# Storage.net
KiCad netlist of a schematic drawn in Altium Designer
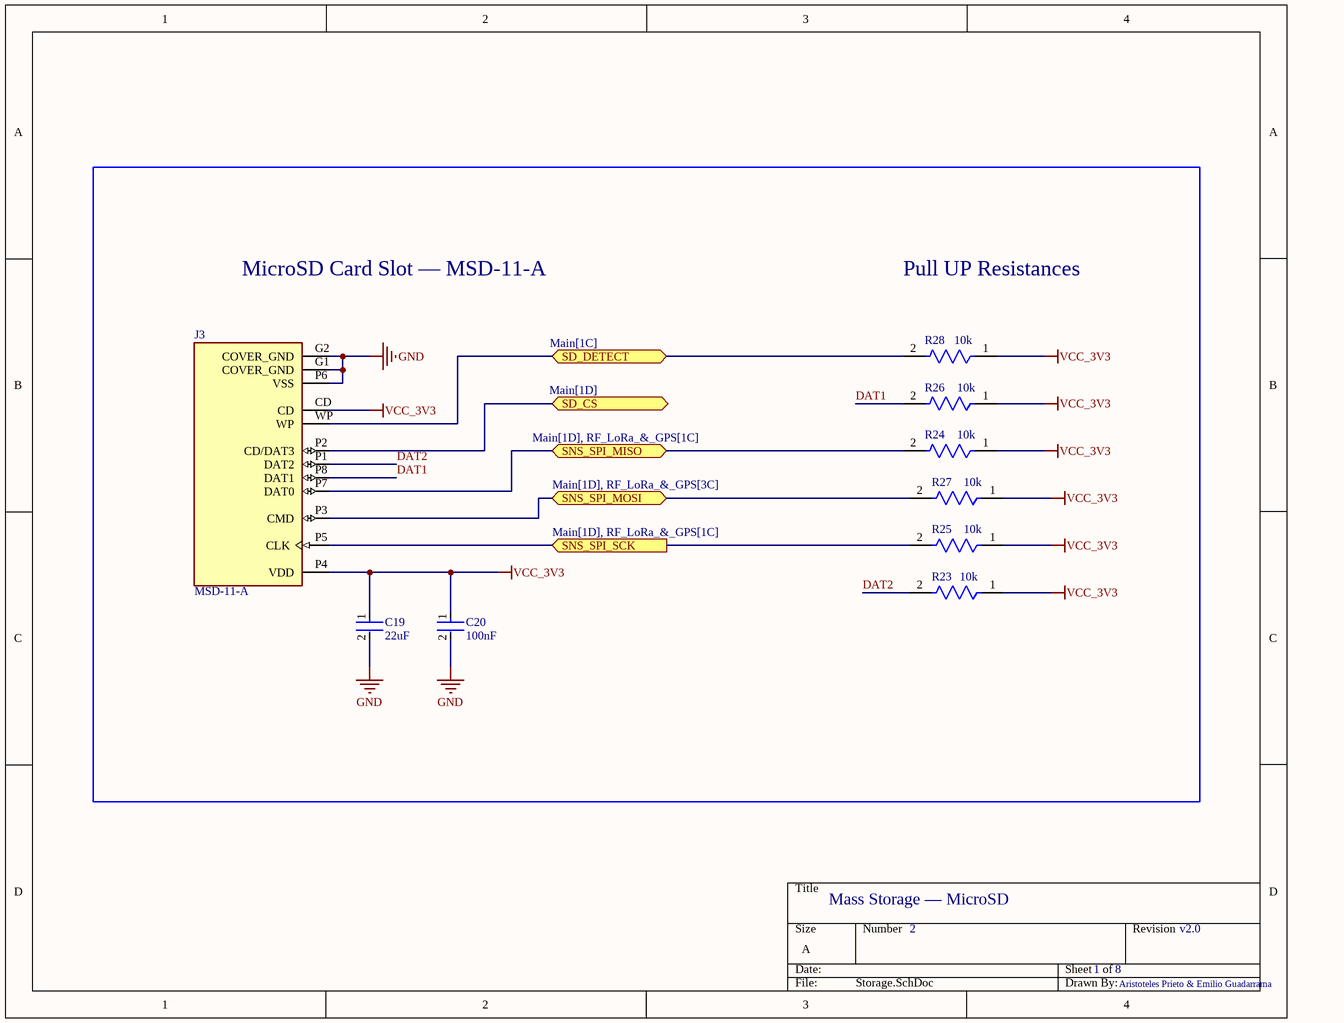
[diagram p0: Storage.SchDoc]

(export (version "E")
  (design (tool "Eeschema 10.0.6"))
  (components
    (comp (ref "C19")
      (value "22uF")
      (footprint "FP-C0805C-DN-MFG")
      (description "CAP CER 0.1UF 50V X7R 0805")
      (fields
        (field (name "MANUFACTURER PART NUMBER") "C0805C104K5RACTU")
        (field (name "MANUFACTURER") "KEMET")
      )
      (libsource (lib "Altium Content Vault") (part "b4654b650e69147ec39a6b967a45e02"))
    )
    (comp (ref "C20")
      (value "100nF")
      (footprint "FP-C0805C-DN-MFG")
      (description "CAP CER 0.1UF 50V X7R 0805")
      (fields
        (field (name "MANUFACTURER PART NUMBER") "C0805C104K5RACTU")
        (field (name "MANUFACTURER") "KEMET")
      )
      (libsource (lib "Altium Content Vault") (part "b4654b650e69147ec39a6b967a45e02"))
    )
    (comp (ref "J3")
      (value "MSD-11-A")
      (footprint "CUI_MSD-11-A")
      (fields (field (name "MF") "Same Sky"))
      (libsource (lib "SD_Holder-MSD-11-A") (part "MSD-11-A"))
    )
    (comp (ref "R23")
      (value "10k")
      (footprint "FP-MCT0603-IPC_A")
      (description "RES SMD 100 OHM 1% 1/8W 0603")
      (fields (field (name "TOLERANCE") "0.1%"))
      (libsource (lib "Altium Content Vault") (part "1029c3af85768c4190bb7ad29bc67b5"))
    )
    (comp (ref "R24")
      (value "10k")
      (footprint "FP-MCT0603-IPC_A")
      (description "RES SMD 100 OHM 1% 1/8W 0603")
      (fields (field (name "TOLERANCE") "0.1%"))
      (libsource (lib "Altium Content Vault") (part "1029c3af85768c4190bb7ad29bc67b5"))
    )
    (comp (ref "R25")
      (value "10k")
      (footprint "FP-MCT0603-IPC_A")
      (description "RES SMD 100 OHM 1% 1/8W 0603")
      (fields (field (name "TOLERANCE") "0.1%"))
      (libsource (lib "Altium Content Vault") (part "1029c3af85768c4190bb7ad29bc67b5"))
    )
    (comp (ref "R26")
      (value "10k")
      (footprint "FP-MCT0603-IPC_A")
      (description "RES SMD 100 OHM 1% 1/8W 0603")
      (fields (field (name "TOLERANCE") "0.1%"))
      (libsource (lib "Altium Content Vault") (part "1029c3af85768c4190bb7ad29bc67b5"))
    )
    (comp (ref "R27")
      (value "10k")
      (footprint "FP-MCT0603-IPC_A")
      (description "RES SMD 100 OHM 1% 1/8W 0603")
      (fields (field (name "TOLERANCE") "0.1%"))
      (libsource (lib "Altium Content Vault") (part "1029c3af85768c4190bb7ad29bc67b5"))
    )
    (comp (ref "R28")
      (value "10k")
      (footprint "FP-MCT0603-IPC_A")
      (description "RES SMD 100 OHM 1% 1/8W 0603")
      (fields (field (name "TOLERANCE") "0.1%"))
      (libsource (lib "Altium Content Vault") (part "1029c3af85768c4190bb7ad29bc67b5"))
    )
  )
  (nets
    (net (code "1") (name "/DAT1") (class "Default")
      (node (ref "J3") (pin "P8") (pinfunction "DAT1_P8") (pintype "bidirectional"))
      (node (ref "R26") (pin "2") (pinfunction "2_2") (pintype "passive"))
    )
    (net (code "2") (name "/DAT2") (class "Default")
      (node (ref "J3") (pin "P1") (pinfunction "DAT2_P1") (pintype "bidirectional"))
      (node (ref "R23") (pin "2") (pinfunction "2_2") (pintype "passive"))
    )
    (net (code "3") (name "/SD_CS") (class "Default")
      (node (ref "J3") (pin "P2") (pinfunction "CD/DAT3_P2") (pintype "bidirectional"))
    )
    (net (code "4") (name "/SD_DETECT") (class "Default")
      (node (ref "J3") (pin "WP") (pinfunction "WP_WP") (pintype "passive"))
      (node (ref "R28") (pin "2") (pinfunction "2_2") (pintype "passive"))
    )
    (net (code "5") (name "/SNS_SPI_MISO") (class "Default")
      (node (ref "J3") (pin "P7") (pinfunction "DAT0_P7") (pintype "bidirectional"))
      (node (ref "R24") (pin "2") (pinfunction "2_2") (pintype "passive"))
    )
    (net (code "6") (name "/SNS_SPI_MOSI") (class "Default")
      (node (ref "J3") (pin "P3") (pinfunction "CMD_P3") (pintype "bidirectional"))
      (node (ref "R27") (pin "2") (pinfunction "2_2") (pintype "passive"))
    )
    (net (code "7") (name "/SNS_SPI_SCK") (class "Default")
      (node (ref "J3") (pin "P5") (pinfunction "CLK_P5") (pintype "input"))
      (node (ref "R25") (pin "2") (pinfunction "2_2") (pintype "passive"))
    )
    (net (code "8") (name "GND") (class "Default")
      (node (ref "C19") (pin "2") (pinfunction "2_2") (pintype "passive"))
      (node (ref "C20") (pin "2") (pinfunction "2_2") (pintype "passive"))
      (node (ref "J3") (pin "G1") (pinfunction "COVER_GND_G1") (pintype "power_in"))
      (node (ref "J3") (pin "G2") (pinfunction "COVER_GND_G2") (pintype "power_in"))
      (node (ref "J3") (pin "P6") (pinfunction "VSS_P6") (pintype "power_in"))
    )
    (net (code "9") (name "VCC_3V3") (class "Default")
      (node (ref "C19") (pin "1") (pinfunction "1_1") (pintype "passive"))
      (node (ref "C20") (pin "1") (pinfunction "1_1") (pintype "passive"))
      (node (ref "J3") (pin "CD") (pinfunction "CD_CD") (pintype "passive"))
      (node (ref "J3") (pin "P4") (pinfunction "VDD_P4") (pintype "power_in"))
      (node (ref "R23") (pin "1") (pinfunction "1_1") (pintype "passive"))
      (node (ref "R24") (pin "1") (pinfunction "1_1") (pintype "passive"))
      (node (ref "R25") (pin "1") (pinfunction "1_1") (pintype "passive"))
      (node (ref "R26") (pin "1") (pinfunction "1_1") (pintype "passive"))
      (node (ref "R27") (pin "1") (pinfunction "1_1") (pintype "passive"))
      (node (ref "R28") (pin "1") (pinfunction "1_1") (pintype "passive"))
    )
  )
)
